# OpenBookReaderC_v7.net
KiCad netlist of a schematic drawn in EAGLE
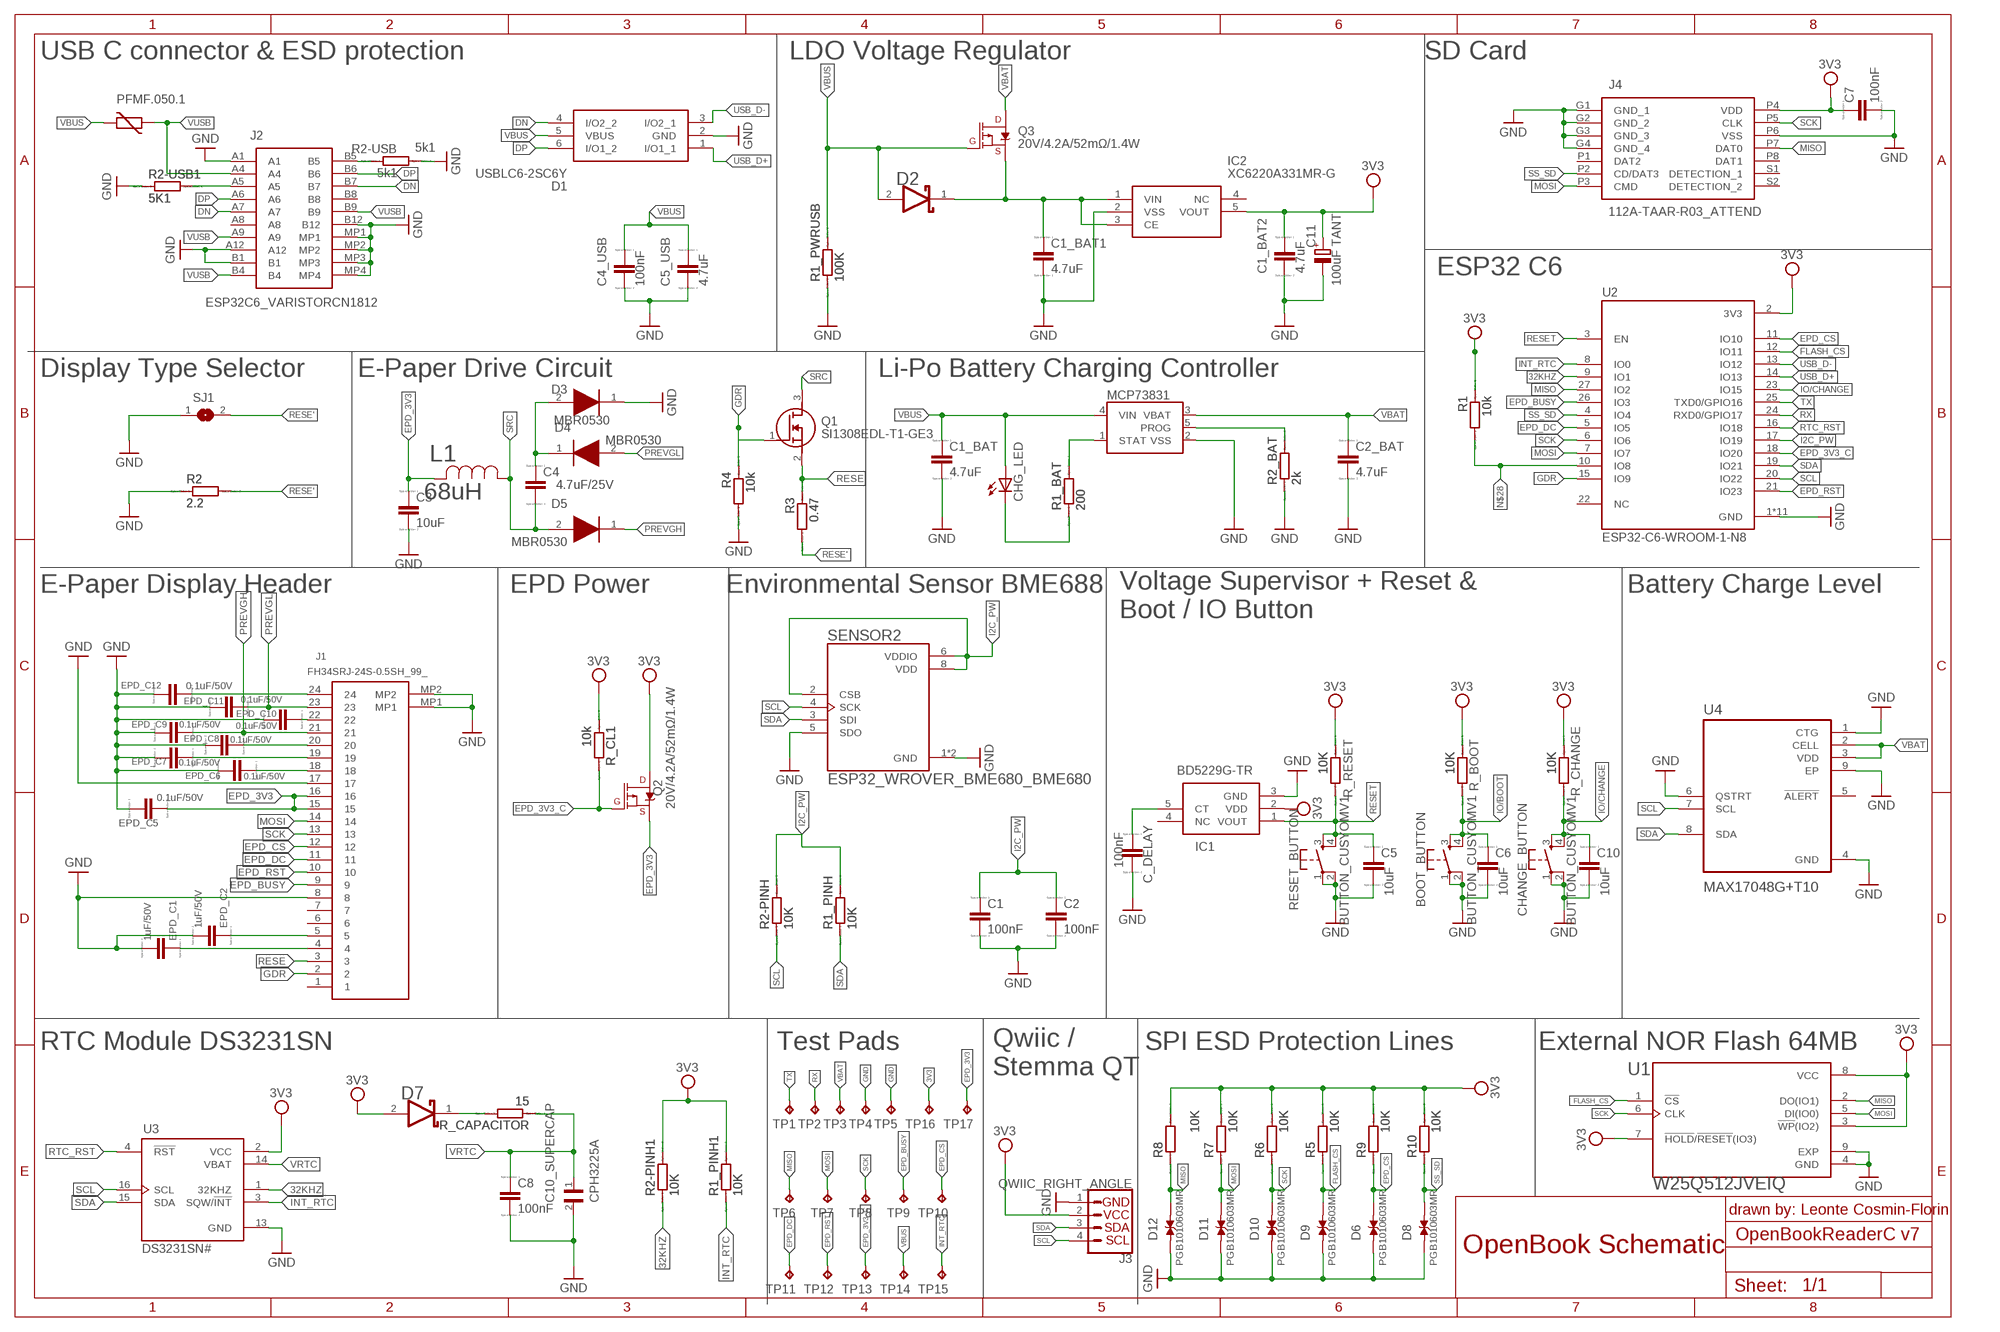
[diagram p0: schematic, sheet 1]

(export (version "E")
  (design (tool "Eeschema 10.0.6"))
  (components
    (comp (ref "BOOT_BUTTON")
      (value "BUTTON_CUSYOMV1")
      (footprint "eagle-import:MYBUTTON")
      (libsource (lib "eagle-import") (part "BUTTON_CUSYOMV1"))
    )
    (comp (ref "C1")
      (value "100nF")
      (footprint "eagle-import:ESP32_WROVER_EAGLE-LTSPICE_C0402")
      (libsource (lib "eagle-import") (part "ESP32_WROVER_EAGLE-LTSPICE_CC0402"))
    )
    (comp (ref "C1_BAT")
      (value "4.7uF")
      (footprint "eagle-import:ESP32_WROVER_EAGLE-LTSPICE_C0402")
      (libsource (lib "eagle-import") (part "ESP32_WROVER_EAGLE-LTSPICE_CC0402"))
    )
    (comp (ref "C1_BAT1")
      (value "4.7uF")
      (footprint "eagle-import:ESP32_WROVER_EAGLE-LTSPICE_C0402")
      (libsource (lib "eagle-import") (part "ESP32_WROVER_EAGLE-LTSPICE_CC0402"))
    )
    (comp (ref "C1_BAT2")
      (value "4.7uF")
      (footprint "eagle-import:ESP32_WROVER_EAGLE-LTSPICE_C0402")
      (libsource (lib "eagle-import") (part "ESP32_WROVER_EAGLE-LTSPICE_CC0402"))
    )
    (comp (ref "C2")
      (value "100nF")
      (footprint "eagle-import:ESP32_WROVER_EAGLE-LTSPICE_C0402")
      (libsource (lib "eagle-import") (part "ESP32_WROVER_EAGLE-LTSPICE_CC0402"))
    )
    (comp (ref "C2_BAT")
      (value "4.7uF")
      (footprint "eagle-import:ESP32_WROVER_EAGLE-LTSPICE_C0402")
      (libsource (lib "eagle-import") (part "ESP32_WROVER_EAGLE-LTSPICE_CC0402"))
    )
    (comp (ref "C3")
      (value "10uF")
      (footprint "eagle-import:ESP32_WROVER_EAGLE-LTSPICE_C0402")
      (libsource (lib "eagle-import") (part "ESP32_WROVER_EAGLE-LTSPICE_CC0402"))
    )
    (comp (ref "C4")
      (value "4.7uF/25V")
      (footprint "eagle-import:ESP32_WROVER_EAGLE-LTSPICE_C0402")
      (libsource (lib "eagle-import") (part "DeskAssistant_v19_v1_vf.EQLOxIDGRNyRrnCg3211Tg_ESP32_WROVER_EAGLE-LTSPICE_CC0402"))
    )
    (comp (ref "C4_USB")
      (value "100nF")
      (footprint "eagle-import:ESP32_WROVER_EAGLE-LTSPICE_C0402")
      (libsource (lib "eagle-import") (part "ESP32_WROVER_EAGLE-LTSPICE_CC0402"))
    )
    (comp (ref "C5")
      (value "10uF")
      (footprint "eagle-import:ESP32_WROVER_EAGLE-LTSPICE_C0402")
      (libsource (lib "eagle-import") (part "ESP32_WROVER_EAGLE-LTSPICE_CC0402"))
    )
    (comp (ref "C5_USB")
      (value "4.7uF")
      (footprint "eagle-import:ESP32_WROVER_EAGLE-LTSPICE_C0402")
      (libsource (lib "eagle-import") (part "ESP32_WROVER_EAGLE-LTSPICE_CC0402"))
    )
    (comp (ref "C6")
      (value "10uF")
      (footprint "eagle-import:ESP32_WROVER_EAGLE-LTSPICE_C0402")
      (libsource (lib "eagle-import") (part "ESP32_WROVER_EAGLE-LTSPICE_CC0402"))
    )
    (comp (ref "C7")
      (value "100nF")
      (footprint "eagle-import:ESP32_WROVER_EAGLE-LTSPICE_C0402")
      (libsource (lib "eagle-import") (part "ESP32_WROVER_EAGLE-LTSPICE_CC0402"))
    )
    (comp (ref "C8")
      (value "100nF")
      (footprint "eagle-import:ESP32_WROVER_EAGLE-LTSPICE_C0402")
      (libsource (lib "eagle-import") (part "ESP32_WROVER_EAGLE-LTSPICE_CC0402"))
    )
    (comp (ref "C10")
      (value "10uF")
      (footprint "eagle-import:ESP32_WROVER_EAGLE-LTSPICE_C0402")
      (libsource (lib "eagle-import") (part "ESP32_WROVER_EAGLE-LTSPICE_CC0402"))
    )
    (comp (ref "C10_SUPERCAP")
      (value "CPH3225A")
      (footprint "eagle-import:CAPCP3225X100N")
      (fields (field (name "MF") "Seiko Instruments"))
      (libsource (lib "eagle-import") (part "CPH3225A"))
    )
    (comp (ref "C11")
      (value "100uF TANT")
      (footprint "eagle-import:RCL_CT3528")
      (libsource (lib "eagle-import") (part "RCL_CPOL-EUCT3528"))
    )
    (comp (ref "CHANGE_BUTTON")
      (value "BUTTON_CUSYOMV1")
      (footprint "eagle-import:MYBUTTON")
      (libsource (lib "eagle-import") (part "BUTTON_CUSYOMV1"))
    )
    (comp (ref "CHG_LED")
      (value "ADAFRUIT_LEDCHIP-LED0603")
      (footprint "eagle-import:ADAFRUIT_CHIP-LED0603")
      (libsource (lib "eagle-import") (part "ADAFRUIT_LEDCHIP-LED0603"))
    )
    (comp (ref "C_DELAY")
      (value "100nF")
      (footprint "eagle-import:ESP32_WROVER_EAGLE-LTSPICE_C0402")
      (libsource (lib "eagle-import") (part "ESP32_WROVER_EAGLE-LTSPICE_CC0402"))
    )
    (comp (ref "D1")
      (value "USBLC6-2SC6Y")
      (footprint "eagle-import:SOT95P280X145-6N")
      (fields (field (name "MF") "STMicroelectronics"))
      (libsource (lib "eagle-import") (part "USBLC6-2SC6Y"))
    )
    (comp (ref "D2")
      (value "ESP32_WROVER_AVX---SD0805S020S1R0_AVX_SD0805S020S1R0_0_0AVX_SD0805S020S1R0_0_0")
      (footprint "eagle-import:ESP32_WROVER_AVX---SD0805S020S1R0_AVX_SD0805S020S1R0_0")
      (fields
        (field (name "DIGIKEY_PART_NUMBER") "478-7800-1-ND")
        (field (name "MF") "AVX")
        (field (name "MOUSER_PART_NUMBER") "581-SD0805S020S1R0")
      )
      (libsource (lib "eagle-import") (part "ESP32_WROVER_AVX---SD0805S020S1R0_AVX_SD0805S020S1R0_0_0AVX_SD0805S020S1R0_0_0"))
    )
    (comp (ref "D3")
      (value "MBR0530")
      (footprint "eagle-import:SOD3716X135N")
      (fields (field (name "MF") "ON Semiconductor"))
      (libsource (lib "eagle-import") (part "MBR0530"))
    )
    (comp (ref "D4")
      (value "MBR0530")
      (footprint "eagle-import:SOD3716X135N")
      (fields (field (name "MF") "ON Semiconductor"))
      (libsource (lib "eagle-import") (part "MBR0530"))
    )
    (comp (ref "D5")
      (value "MBR0530")
      (footprint "eagle-import:SOD3716X135N")
      (fields (field (name "MF") "ON Semiconductor"))
      (libsource (lib "eagle-import") (part "MBR0530"))
    )
    (comp (ref "D6")
      (value "PGB1010603MR")
      (footprint "eagle-import:DIOC1608X36N")
      (fields (field (name "MF") "Littelfuse Inc."))
      (libsource (lib "eagle-import") (part "PGB1010603MR"))
    )
    (comp (ref "D7")
      (value "ESP32_WROVER_AVX---SD0805S020S1R0_AVX_SD0805S020S1R0_0_0AVX_SD0805S020S1R0_0_0")
      (footprint "eagle-import:ESP32_WROVER_AVX---SD0805S020S1R0_AVX_SD0805S020S1R0_0")
      (fields
        (field (name "DIGIKEY_PART_NUMBER") "478-7800-1-ND")
        (field (name "MF") "AVX")
        (field (name "MOUSER_PART_NUMBER") "581-SD0805S020S1R0")
      )
      (libsource (lib "eagle-import") (part "ESP32_WROVER_AVX---SD0805S020S1R0_AVX_SD0805S020S1R0_0_0AVX_SD0805S020S1R0_0_0"))
    )
    (comp (ref "D8")
      (value "PGB1010603MR")
      (footprint "eagle-import:DIOC1608X36N")
      (fields (field (name "MF") "Littelfuse Inc."))
      (libsource (lib "eagle-import") (part "PGB1010603MR"))
    )
    (comp (ref "D9")
      (value "PGB1010603MR")
      (footprint "eagle-import:DIOC1608X36N")
      (fields (field (name "MF") "Littelfuse Inc."))
      (libsource (lib "eagle-import") (part "PGB1010603MR"))
    )
    (comp (ref "D10")
      (value "PGB1010603MR")
      (footprint "eagle-import:DIOC1608X36N")
      (fields (field (name "MF") "Littelfuse Inc."))
      (libsource (lib "eagle-import") (part "PGB1010603MR"))
    )
    (comp (ref "D11")
      (value "PGB1010603MR")
      (footprint "eagle-import:DIOC1608X36N")
      (fields (field (name "MF") "Littelfuse Inc."))
      (libsource (lib "eagle-import") (part "PGB1010603MR"))
    )
    (comp (ref "D12")
      (value "PGB1010603MR")
      (footprint "eagle-import:DIOC1608X36N")
      (fields (field (name "MF") "Littelfuse Inc."))
      (libsource (lib "eagle-import") (part "PGB1010603MR"))
    )
    (comp (ref "EPD_C1")
      (value "1uF/50V")
      (footprint "eagle-import:ESP32_WROVER_EAGLE-LTSPICE_C0402")
      (libsource (lib "eagle-import") (part "ESP32_WROVER_EAGLE-LTSPICE_CC0402"))
    )
    (comp (ref "EPD_C2")
      (value "1uF/50V")
      (footprint "eagle-import:ESP32_WROVER_EAGLE-LTSPICE_C0402")
      (libsource (lib "eagle-import") (part "ESP32_WROVER_EAGLE-LTSPICE_CC0402"))
    )
    (comp (ref "EPD_C5")
      (value "0.1uF/50V")
      (footprint "eagle-import:ESP32_WROVER_EAGLE-LTSPICE_C0402")
      (libsource (lib "eagle-import") (part "ESP32_WROVER_EAGLE-LTSPICE_CC0402"))
    )
    (comp (ref "EPD_C6")
      (value "0.1uF/50V")
      (footprint "eagle-import:ESP32_WROVER_EAGLE-LTSPICE_C0402")
      (libsource (lib "eagle-import") (part "ESP32_WROVER_EAGLE-LTSPICE_CC0402"))
    )
    (comp (ref "EPD_C7")
      (value "0.1uF/50V")
      (footprint "eagle-import:ESP32_WROVER_EAGLE-LTSPICE_C0402")
      (libsource (lib "eagle-import") (part "ESP32_WROVER_EAGLE-LTSPICE_CC0402"))
    )
    (comp (ref "EPD_C8")
      (value "0.1uF/50V")
      (footprint "eagle-import:ESP32_WROVER_EAGLE-LTSPICE_C0402")
      (libsource (lib "eagle-import") (part "ESP32_WROVER_EAGLE-LTSPICE_CC0402"))
    )
    (comp (ref "EPD_C9")
      (value "0.1uF/50V")
      (footprint "eagle-import:ESP32_WROVER_EAGLE-LTSPICE_C0402")
      (libsource (lib "eagle-import") (part "ESP32_WROVER_EAGLE-LTSPICE_CC0402"))
    )
    (comp (ref "EPD_C10")
      (value "0.1uF/50V")
      (footprint "eagle-import:ESP32_WROVER_EAGLE-LTSPICE_C0402")
      (libsource (lib "eagle-import") (part "ESP32_WROVER_EAGLE-LTSPICE_CC0402"))
    )
    (comp (ref "EPD_C11")
      (value "0.1uF/50V")
      (footprint "eagle-import:ESP32_WROVER_EAGLE-LTSPICE_C0402")
      (libsource (lib "eagle-import") (part "ESP32_WROVER_EAGLE-LTSPICE_CC0402"))
    )
    (comp (ref "EPD_C12")
      (value "0.1uF/50V")
      (footprint "eagle-import:ESP32_WROVER_EAGLE-LTSPICE_C0402")
      (libsource (lib "eagle-import") (part "ESP32_WROVER_EAGLE-LTSPICE_CC0402"))
    )
    (comp (ref "IC1")
      (value "BD5229G-TR")
      (footprint "eagle-import:SOT95P280X125-5N")
      (fields (field (name "MOUSER_PART_NUMBER") "755-BD5229G-TR"))
      (libsource (lib "eagle-import") (part "BD5229G-TR"))
    )
    (comp (ref "IC2")
      (value "XC6220A331MR-G")
      (footprint "eagle-import:SOT95P280X120-5N")
      (fields (field (name "MOUSER_PART_NUMBER") "865-XC6220A331MR-G"))
      (libsource (lib "eagle-import") (part "XC6220A331MR-G"))
    )
    (comp (ref "J1")
      (value "FH34SRJ-24S-0.5SH_99_")
      (footprint "eagle-import:FH34SRJ24S05SH99")
      (fields
        (field (name "MANUFACTURER_PART_NUMBER") "FH34SRJ-24S-0.5SH(99)")
        (field (name "MOUSER_PART_NUMBER") "798-FH34SRJ24S05SH99")
      )
      (libsource (lib "eagle-import") (part "FH34SRJ-24S-0.5SH_99_"))
    )
    (comp (ref "J2")
      (value "SAMACSYS_PARTS_USB4110-GF-A")
      (footprint "eagle-import:SAMACSYS_PARTS_USB4110GFA")
      (fields
        (field (name "MANUFACTURER_PART_NUMBER") "USB4110-GF-A")
        (field (name "MOUSER_PART_NUMBER") "640-USB4110-GF-A")
      )
      (libsource (lib "eagle-import") (part "SAMACSYS_PARTS_USB4110-GF-A"))
    )
    (comp (ref "J3")
      (value "QWIIC_RIGHT_ANGLE")
      (footprint "eagle-import:JST04_1MM_RA")
      (libsource (lib "eagle-import") (part "QWIIC_CONNECTORJS-1MM"))
    )
    (comp (ref "J4")
      (value "112A-TAAR-R03_ATTEND")
      (footprint "eagle-import:112ATAARR03ATTEND")
      (fields (field (name "MANUFACTURER_PART_NUMBER") "112A-TAAR-R03 ATTEND"))
      (libsource (lib "eagle-import") (part "112A-TAAR-R03_ATTEND"))
    )
    (comp (ref "L1")
      (value "68uH")
      (footprint "eagle-import:IND_4828-WE-TPC_WRE")
      (fields
        (field (name "MANUFACTURER_PART_NUMBER") "744043680")
        (field (name "COPYRIGHT") "Copyright (C) 2024 Ultra Librarian. All rights reserved.")
      )
      (libsource (lib "eagle-import") (part "744043680IND_4828-WE-TPC_WRE"))
    )
    (comp (ref "MCP73831")
      (value "ESP32_WROVER_SPARKFUN-IC-POWER_MCP73831")
      (footprint "eagle-import:ESP32_WROVER_SPARKFUN-IC-POWER_SOT23-5")
      (libsource (lib "eagle-import") (part "ESP32_WROVER_SPARKFUN-IC-POWER_MCP73831"))
    )
    (comp (ref "PFMF.050.1")
      (value "ESP32C6_VARISTORCN1812")
      (footprint "eagle-import:ESP32C6_VARISTOR_CT_CN1812")
      (libsource (lib "eagle-import") (part "ESP32C6_VARISTORCN1812"))
    )
    (comp (ref "Q1")
      (value "SI1308EDL-T1-GE3")
      (footprint "eagle-import:SOT65P210X110-3N")
      (fields (field (name "MF") "Vishay Siliconix"))
      (libsource (lib "eagle-import") (part "SI1308EDL-T1-GE3"))
    )
    (comp (ref "Q2")
      (value "20V/4.2A/52mΩ/1.4W")
      (footprint "eagle-import:ESP32_WROVER_SPARKFUN-DISCRETESEMI_SOT23-3")
      (libsource (lib "eagle-import") (part "ESP32_WROVER_SPARKFUN-DISCRETESEMI_MOSFET_PCH-DMG2305UX-7"))
    )
    (comp (ref "Q3")
      (value "20V/4.2A/52mΩ/1.4W")
      (footprint "eagle-import:ESP32_WROVER_SPARKFUN-DISCRETESEMI_SOT23-3")
      (libsource (lib "eagle-import") (part "ESP32_WROVER_SPARKFUN-DISCRETESEMI_MOSFET_PCH-DMG2305UX-7"))
    )
    (comp (ref "R1")
      (value "10k")
      (footprint "eagle-import:ESP32_WROVER_EAGLE-LTSPICE_R0402")
      (libsource (lib "eagle-import") (part "DeskAssistant_v19_v1_vf.EQLOxIDGRNyRrnCg3211Tg_ESP32_WROVER_EAGLE-LTSPICE_RR0402"))
    )
    (comp (ref "R1_BAT")
      (value "200")
      (footprint "eagle-import:ESP32_WROVER_EAGLE-LTSPICE_R0402")
      (libsource (lib "eagle-import") (part "DeskAssistant_v19_v1_vf.EQLOxIDGRNyRrnCg3211Tg_ESP32_WROVER_EAGLE-LTSPICE_RR0402"))
    )
    (comp (ref "R1_PINH")
      (value "10K")
      (footprint "eagle-import:ESP32_WROVER_EAGLE-LTSPICE_R0402")
      (libsource (lib "eagle-import") (part "DeskAssistant_v19_v1_vf.EQLOxIDGRNyRrnCg3211Tg_ESP32_WROVER_EAGLE-LTSPICE_RR0402"))
    )
    (comp (ref "R1_PINH1")
      (value "10K")
      (footprint "eagle-import:ESP32_WROVER_EAGLE-LTSPICE_R0402")
      (libsource (lib "eagle-import") (part "DeskAssistant_v19_v1_vf.EQLOxIDGRNyRrnCg3211Tg_ESP32_WROVER_EAGLE-LTSPICE_RR0402"))
    )
    (comp (ref "R1_PWRUSB")
      (value "100K")
      (footprint "eagle-import:ESP32_WROVER_EAGLE-LTSPICE_R0402")
      (libsource (lib "eagle-import") (part "DeskAssistant_v19_v1_vf.EQLOxIDGRNyRrnCg3211Tg_ESP32_WROVER_EAGLE-LTSPICE_RR0402"))
    )
    (comp (ref "R2")
      (value "2.2")
      (footprint "eagle-import:ESP32_WROVER_EAGLE-LTSPICE_R0402")
      (libsource (lib "eagle-import") (part "DeskAssistant_v19_v1_vf.EQLOxIDGRNyRrnCg3211Tg_ESP32_WROVER_EAGLE-LTSPICE_RR0402"))
    )
    (comp (ref "R2-PINH")
      (value "10K")
      (footprint "eagle-import:ESP32_WROVER_EAGLE-LTSPICE_R0402")
      (libsource (lib "eagle-import") (part "DeskAssistant_v19_v1_vf.EQLOxIDGRNyRrnCg3211Tg_ESP32_WROVER_EAGLE-LTSPICE_RR0402"))
    )
    (comp (ref "R2-PINH1")
      (value "10K")
      (footprint "eagle-import:ESP32_WROVER_EAGLE-LTSPICE_R0402")
      (libsource (lib "eagle-import") (part "DeskAssistant_v19_v1_vf.EQLOxIDGRNyRrnCg3211Tg_ESP32_WROVER_EAGLE-LTSPICE_RR0402"))
    )
    (comp (ref "R2-USB")
      (value "5k1")
      (footprint "eagle-import:ESP32_WROVER_EAGLE-LTSPICE_R0402")
      (libsource (lib "eagle-import") (part "DeskAssistant_v19_v1_vf.EQLOxIDGRNyRrnCg3211Tg_ESP32_WROVER_EAGLE-LTSPICE_RR0402"))
    )
    (comp (ref "R2-USB1")
      (value "5K1")
      (footprint "eagle-import:ESP32_WROVER_EAGLE-LTSPICE_R0402")
      (libsource (lib "eagle-import") (part "DeskAssistant_v19_v1_vf.EQLOxIDGRNyRrnCg3211Tg_ESP32_WROVER_EAGLE-LTSPICE_RR0402"))
    )
    (comp (ref "R2_BAT")
      (value "2k")
      (footprint "eagle-import:ESP32_WROVER_EAGLE-LTSPICE_R0402")
      (libsource (lib "eagle-import") (part "DeskAssistant_v19_v1_vf.EQLOxIDGRNyRrnCg3211Tg_ESP32_WROVER_EAGLE-LTSPICE_RR0402"))
    )
    (comp (ref "R3")
      (value "0.47")
      (footprint "eagle-import:ESP32_WROVER_EAGLE-LTSPICE_R0402")
      (libsource (lib "eagle-import") (part "ESP32_WROVER_EAGLE-LTSPICE_RR0402"))
    )
    (comp (ref "R4")
      (value "10k")
      (footprint "eagle-import:ESP32_WROVER_EAGLE-LTSPICE_R0402")
      (libsource (lib "eagle-import") (part "ESP32_WROVER_EAGLE-LTSPICE_RR0402"))
    )
    (comp (ref "R5")
      (value "10K")
      (footprint "eagle-import:ESP32_WROVER_EAGLE-LTSPICE_R0402")
      (libsource (lib "eagle-import") (part "DeskAssistant_v19_v1_vf.EQLOxIDGRNyRrnCg3211Tg_ESP32_WROVER_EAGLE-LTSPICE_RR0402"))
    )
    (comp (ref "R6")
      (value "10K")
      (footprint "eagle-import:ESP32_WROVER_EAGLE-LTSPICE_R0402")
      (libsource (lib "eagle-import") (part "DeskAssistant_v19_v1_vf.EQLOxIDGRNyRrnCg3211Tg_ESP32_WROVER_EAGLE-LTSPICE_RR0402"))
    )
    (comp (ref "R7")
      (value "10K")
      (footprint "eagle-import:ESP32_WROVER_EAGLE-LTSPICE_R0402")
      (libsource (lib "eagle-import") (part "DeskAssistant_v19_v1_vf.EQLOxIDGRNyRrnCg3211Tg_ESP32_WROVER_EAGLE-LTSPICE_RR0402"))
    )
    (comp (ref "R8")
      (value "10K")
      (footprint "eagle-import:ESP32_WROVER_EAGLE-LTSPICE_R0402")
      (libsource (lib "eagle-import") (part "DeskAssistant_v19_v1_vf.EQLOxIDGRNyRrnCg3211Tg_ESP32_WROVER_EAGLE-LTSPICE_RR0402"))
    )
    (comp (ref "R9")
      (value "10K")
      (footprint "eagle-import:ESP32_WROVER_EAGLE-LTSPICE_R0402")
      (libsource (lib "eagle-import") (part "DeskAssistant_v19_v1_vf.EQLOxIDGRNyRrnCg3211Tg_ESP32_WROVER_EAGLE-LTSPICE_RR0402"))
    )
    (comp (ref "R10")
      (value "10K")
      (footprint "eagle-import:ESP32_WROVER_EAGLE-LTSPICE_R0402")
      (libsource (lib "eagle-import") (part "DeskAssistant_v19_v1_vf.EQLOxIDGRNyRrnCg3211Tg_ESP32_WROVER_EAGLE-LTSPICE_RR0402"))
    )
    (comp (ref "RESET_BUTTON")
      (value "BUTTON_CUSYOMV1")
      (footprint "eagle-import:MYBUTTON")
      (libsource (lib "eagle-import") (part "BUTTON_CUSYOMV1"))
    )
    (comp (ref "R_BOOT")
      (value "10K")
      (footprint "eagle-import:ESP32_WROVER_EAGLE-LTSPICE_R0402")
      (libsource (lib "eagle-import") (part "DeskAssistant_v19_v1_vf.EQLOxIDGRNyRrnCg3211Tg_ESP32_WROVER_EAGLE-LTSPICE_RR0402"))
    )
    (comp (ref "R_CAPACITOR")
      (value "15")
      (footprint "eagle-import:ESP32_WROVER_EAGLE-LTSPICE_R0402")
      (libsource (lib "eagle-import") (part "DeskAssistant_v19_v1_vf.EQLOxIDGRNyRrnCg3211Tg_ESP32_WROVER_EAGLE-LTSPICE_RR0402"))
    )
    (comp (ref "R_CHANGE")
      (value "10K")
      (footprint "eagle-import:ESP32_WROVER_EAGLE-LTSPICE_R0402")
      (libsource (lib "eagle-import") (part "DeskAssistant_v19_v1_vf.EQLOxIDGRNyRrnCg3211Tg_ESP32_WROVER_EAGLE-LTSPICE_RR0402"))
    )
    (comp (ref "R_CL1")
      (value "10k")
      (footprint "eagle-import:ESP32_WROVER_EAGLE-LTSPICE_R0402")
      (libsource (lib "eagle-import") (part "DeskAssistant_v19_v1_vf.EQLOxIDGRNyRrnCg3211Tg_ESP32_WROVER_EAGLE-LTSPICE_RR0402"))
    )
    (comp (ref "R_RESET")
      (value "10K")
      (footprint "eagle-import:ESP32_WROVER_EAGLE-LTSPICE_R0402")
      (libsource (lib "eagle-import") (part "DeskAssistant_v19_v1_vf.EQLOxIDGRNyRrnCg3211Tg_ESP32_WROVER_EAGLE-LTSPICE_RR0402"))
    )
    (comp (ref "SENSOR2")
      (value "ESP32_WROVER_BME680_BME680")
      (footprint "eagle-import:ESP32_WROVER_BME680_PSON80P300X300X100-8N")
      (fields (field (name "MF") "Bosch Sensortec") (field (name "MP") "BME680"))
      (libsource (lib "eagle-import") (part "ESP32_WROVER_BME680_BME680"))
    )
    (comp (ref "SJ1") (value "SJ") (footprint "eagle-import:SJ") (libsource (lib "eagle-import") (part "SJ")))
    (comp (ref "TP1")
      (value "TPTP20R")
      (footprint "eagle-import:TP20R")
      (libsource (lib "eagle-import") (part "TPTP20R"))
    )
    (comp (ref "TP2")
      (value "TPTP20R")
      (footprint "eagle-import:TP20R")
      (libsource (lib "eagle-import") (part "TPTP20R"))
    )
    (comp (ref "TP3")
      (value "TPTP20R")
      (footprint "eagle-import:TP20R")
      (libsource (lib "eagle-import") (part "TPTP20R"))
    )
    (comp (ref "TP4")
      (value "TPTP20R")
      (footprint "eagle-import:TP20R")
      (libsource (lib "eagle-import") (part "TPTP20R"))
    )
    (comp (ref "TP5")
      (value "TPTP20R")
      (footprint "eagle-import:TP20R")
      (libsource (lib "eagle-import") (part "TPTP20R"))
    )
    (comp (ref "TP6")
      (value "TPTP20R")
      (footprint "eagle-import:TP20R")
      (libsource (lib "eagle-import") (part "TPTP20R"))
    )
    (comp (ref "TP7")
      (value "TPTP20R")
      (footprint "eagle-import:TP20R")
      (libsource (lib "eagle-import") (part "TPTP20R"))
    )
    (comp (ref "TP8")
      (value "TPTP20R")
      (footprint "eagle-import:TP20R")
      (libsource (lib "eagle-import") (part "TPTP20R"))
    )
    (comp (ref "TP9")
      (value "TPTP20R")
      (footprint "eagle-import:TP20R")
      (libsource (lib "eagle-import") (part "TPTP20R"))
    )
    (comp (ref "TP10")
      (value "TPTP20R")
      (footprint "eagle-import:TP20R")
      (libsource (lib "eagle-import") (part "TPTP20R"))
    )
    (comp (ref "TP11")
      (value "TPTP20R")
      (footprint "eagle-import:TP20R")
      (libsource (lib "eagle-import") (part "TPTP20R"))
    )
    (comp (ref "TP12")
      (value "TPTP20R")
      (footprint "eagle-import:TP20R")
      (libsource (lib "eagle-import") (part "TPTP20R"))
    )
    (comp (ref "TP13")
      (value "TPTP20R")
      (footprint "eagle-import:TP20R")
      (libsource (lib "eagle-import") (part "TPTP20R"))
    )
    (comp (ref "TP14")
      (value "TPTP20R")
      (footprint "eagle-import:TP20R")
      (libsource (lib "eagle-import") (part "TPTP20R"))
    )
    (comp (ref "TP15")
      (value "TPTP20R")
      (footprint "eagle-import:TP20R")
      (libsource (lib "eagle-import") (part "TPTP20R"))
    )
    (comp (ref "TP16")
      (value "TPTP20R")
      (footprint "eagle-import:TP20R")
      (libsource (lib "eagle-import") (part "TPTP20R"))
    )
    (comp (ref "TP17")
      (value "TPTP20R")
      (footprint "eagle-import:TP20R")
      (libsource (lib "eagle-import") (part "TPTP20R"))
    )
    (comp (ref "U1")
      (value "W25Q512JVEIQ")
      (footprint "eagle-import:SON127P600X800X80-9N")
      (fields (field (name "MF") "Winbond Electronics"))
      (libsource (lib "eagle-import") (part "W25Q512JVEIQ"))
    )
    (comp (ref "U2")
      (value "ESP32-C6-WROOM-1-N8")
      (footprint "eagle-import:XCVR_ESP32-C6-WROOM-1-N8")
      (fields (field (name "MF") "Espressif Systems"))
      (libsource (lib "eagle-import") (part "ESP32-C6-WROOM-1-N8"))
    )
    (comp (ref "U3")
      (value "DS3231SN#")
      (footprint "eagle-import:SOIC127P1032X265-16N")
      (fields (field (name "MF") "Analog Devices"))
      (libsource (lib "eagle-import") (part "DS3231SN#"))
    )
    (comp (ref "U4")
      (value "MAX17048G+T10")
      (footprint "eagle-import:SON50P200X200X80-9N")
      (fields (field (name "MF") "Analog Devices"))
      (libsource (lib "eagle-import") (part "MAX17048G+T10"))
    )
  )
  (nets
    (net (code "1") (name "3V3") (class "Default")
      (node (ref "C11") (pin "+") (pinfunction "+_+") (pintype "passive"))
      (node (ref "C1_BAT2") (pin "1") (pinfunction "1_1") (pintype "passive"))
      (node (ref "C7") (pin "1") (pinfunction "1_1") (pintype "passive"))
      (node (ref "D7") (pin "2") (pinfunction "ANODE_2") (pintype "bidirectional"))
      (node (ref "IC1") (pin "2") (pinfunction "VDD_2") (pintype "bidirectional"))
      (node (ref "IC2") (pin "5") (pinfunction "VOUT_5") (pintype "bidirectional"))
      (node (ref "J3") (pin "2") (pinfunction "2_2") (pintype "power_in"))
      (node (ref "J4") (pin "P4") (pinfunction "VDD_P4") (pintype "bidirectional"))
      (node (ref "Q2") (pin "3") (pinfunction "D_3") (pintype "bidirectional"))
      (node (ref "R1") (pin "1") (pinfunction "1_1") (pintype "passive"))
      (node (ref "R10") (pin "2") (pinfunction "2_2") (pintype "passive"))
      (node (ref "R1_PINH1") (pin "2") (pinfunction "2_2") (pintype "passive"))
      (node (ref "R2-PINH1") (pin "2") (pinfunction "2_2") (pintype "passive"))
      (node (ref "R5") (pin "2") (pinfunction "2_2") (pintype "passive"))
      (node (ref "R6") (pin "2") (pinfunction "2_2") (pintype "passive"))
      (node (ref "R7") (pin "2") (pinfunction "2_2") (pintype "passive"))
      (node (ref "R8") (pin "2") (pinfunction "2_2") (pintype "passive"))
      (node (ref "R9") (pin "2") (pinfunction "2_2") (pintype "passive"))
      (node (ref "R_BOOT") (pin "1") (pinfunction "1_1") (pintype "passive"))
      (node (ref "R_CHANGE") (pin "1") (pinfunction "1_1") (pintype "passive"))
      (node (ref "R_CL1") (pin "1") (pinfunction "1_1") (pintype "passive"))
      (node (ref "R_RESET") (pin "1") (pinfunction "1_1") (pintype "passive"))
      (node (ref "TP16") (pin "TP") (pinfunction "TP_TP") (pintype "input"))
      (node (ref "U1") (pin "3") (pinfunction "~{WP}(IO2)_3") (pintype "bidirectional"))
      (node (ref "U1") (pin "7") (pinfunction "~{HOLD}/~{RESET}(IO3)_7") (pintype "bidirectional"))
      (node (ref "U1") (pin "8") (pinfunction "VCC_8") (pintype "power_in"))
      (node (ref "U2") (pin "2") (pinfunction "3V3_2") (pintype "power_in"))
      (node (ref "U3") (pin "2") (pinfunction "VCC_2") (pintype "power_in"))
    )
    (net (code "2") (name "32KHZ") (class "Default")
      (node (ref "R2-PINH1") (pin "1") (pinfunction "1_1") (pintype "passive"))
      (node (ref "U2") (pin "9") (pinfunction "IO1_9") (pintype "bidirectional"))
      (node (ref "U3") (pin "1") (pinfunction "32KHZ_1") (pintype "output"))
    )
    (net (code "3") (name "DN") (class "Default")
      (node (ref "D1") (pin "4") (pinfunction "I/O2_2_4") (pintype "bidirectional"))
      (node (ref "J2") (pin "A7") (pinfunction "A7_A7") (pintype "bidirectional"))
      (node (ref "J2") (pin "B7") (pinfunction "B7_B7") (pintype "bidirectional"))
    )
    (net (code "4") (name "DP") (class "Default")
      (node (ref "D1") (pin "6") (pinfunction "I/O1_2_6") (pintype "bidirectional"))
      (node (ref "J2") (pin "A6") (pinfunction "A6_A6") (pintype "bidirectional"))
      (node (ref "J2") (pin "B6") (pinfunction "B6_B6") (pintype "bidirectional"))
    )
    (net (code "5") (name "EPD_3V3") (class "Default")
      (node (ref "C3") (pin "1") (pinfunction "1_1") (pintype "passive"))
      (node (ref "EPD_C5") (pin "1") (pinfunction "1_1") (pintype "passive"))
      (node (ref "J1") (pin "15") (pinfunction "15_15") (pintype "bidirectional"))
      (node (ref "J1") (pin "16") (pinfunction "16_16") (pintype "bidirectional"))
      (node (ref "L1") (pin "2") (pinfunction "2_2") (pintype "passive"))
      (node (ref "Q2") (pin "2") (pinfunction "S_2") (pintype "bidirectional"))
      (node (ref "TP17") (pin "TP") (pinfunction "TP_TP") (pintype "input"))
    )
    (net (code "6") (name "EPD_3V3_C") (class "Default")
      (node (ref "Q2") (pin "1") (pinfunction "G_1") (pintype "bidirectional"))
      (node (ref "R_CL1") (pin "2") (pinfunction "2_2") (pintype "passive"))
      (node (ref "TP13") (pin "TP") (pinfunction "TP_TP") (pintype "input"))
      (node (ref "U2") (pin "18") (pinfunction "IO20_18") (pintype "bidirectional"))
    )
    (net (code "7") (name "EPD_BUSY") (class "Default")
      (node (ref "J1") (pin "9") (pinfunction "9_9") (pintype "bidirectional"))
      (node (ref "TP9") (pin "TP") (pinfunction "TP_TP") (pintype "input"))
      (node (ref "U2") (pin "26") (pinfunction "IO3_26") (pintype "bidirectional"))
    )
    (net (code "8") (name "EPD_CS") (class "Default")
      (node (ref "D6") (pin "2") (pinfunction "2_2") (pintype "passive"))
      (node (ref "J1") (pin "12") (pinfunction "12_12") (pintype "bidirectional"))
      (node (ref "R9") (pin "1") (pinfunction "1_1") (pintype "passive"))
      (node (ref "TP10") (pin "TP") (pinfunction "TP_TP") (pintype "input"))
      (node (ref "U2") (pin "11") (pinfunction "IO10_11") (pintype "bidirectional"))
    )
    (net (code "9") (name "EPD_DC") (class "Default")
      (node (ref "J1") (pin "11") (pinfunction "11_11") (pintype "bidirectional"))
      (node (ref "TP11") (pin "TP") (pinfunction "TP_TP") (pintype "input"))
      (node (ref "U2") (pin "5") (pinfunction "IO5_5") (pintype "bidirectional"))
    )
    (net (code "10") (name "EPD_RST") (class "Default")
      (node (ref "J1") (pin "10") (pinfunction "10_10") (pintype "bidirectional"))
      (node (ref "TP12") (pin "TP") (pinfunction "TP_TP") (pintype "input"))
      (node (ref "U2") (pin "21") (pinfunction "IO23_21") (pintype "bidirectional"))
    )
    (net (code "11") (name "FLASH_CS") (class "Default")
      (node (ref "D9") (pin "2") (pinfunction "2_2") (pintype "passive"))
      (node (ref "R5") (pin "1") (pinfunction "1_1") (pintype "passive"))
      (node (ref "U1") (pin "1") (pinfunction "~{CS}_1") (pintype "input"))
      (node (ref "U2") (pin "12") (pinfunction "IO11_12") (pintype "bidirectional"))
    )
    (net (code "12") (name "GDR") (class "Default")
      (node (ref "J1") (pin "2") (pinfunction "2_2") (pintype "bidirectional"))
      (node (ref "Q1") (pin "1") (pinfunction "G_1") (pintype "bidirectional"))
      (node (ref "R4") (pin "1") (pinfunction "1_1") (pintype "passive"))
      (node (ref "U2") (pin "15") (pinfunction "IO9_15") (pintype "bidirectional"))
    )
    (net (code "13") (name "GND") (class "Default")
      (node (ref "BOOT_BUTTON") (pin "1") (pinfunction "1_1") (pintype "passive"))
      (node (ref "BOOT_BUTTON") (pin "2") (pinfunction "2_2") (pintype "passive"))
      (node (ref "C1") (pin "2") (pinfunction "2_2") (pintype "passive"))
      (node (ref "C10") (pin "2") (pinfunction "2_2") (pintype "passive"))
      (node (ref "C10_SUPERCAP") (pin "2") (pinfunction "2_2") (pintype "passive"))
      (node (ref "C11") (pin "-") (pinfunction "-_-") (pintype "passive"))
      (node (ref "C1_BAT") (pin "2") (pinfunction "2_2") (pintype "passive"))
      (node (ref "C1_BAT1") (pin "2") (pinfunction "2_2") (pintype "passive"))
      (node (ref "C1_BAT2") (pin "2") (pinfunction "2_2") (pintype "passive"))
      (node (ref "C2") (pin "2") (pinfunction "2_2") (pintype "passive"))
      (node (ref "C2_BAT") (pin "2") (pinfunction "2_2") (pintype "passive"))
      (node (ref "C3") (pin "2") (pinfunction "2_2") (pintype "passive"))
      (node (ref "C4_USB") (pin "2") (pinfunction "2_2") (pintype "passive"))
      (node (ref "C5") (pin "2") (pinfunction "2_2") (pintype "passive"))
      (node (ref "C5_USB") (pin "2") (pinfunction "2_2") (pintype "passive"))
      (node (ref "C6") (pin "2") (pinfunction "2_2") (pintype "passive"))
      (node (ref "C7") (pin "2") (pinfunction "2_2") (pintype "passive"))
      (node (ref "C8") (pin "2") (pinfunction "2_2") (pintype "passive"))
      (node (ref "CHANGE_BUTTON") (pin "1") (pinfunction "1_1") (pintype "passive"))
      (node (ref "CHANGE_BUTTON") (pin "2") (pinfunction "2_2") (pintype "passive"))
      (node (ref "C_DELAY") (pin "2") (pinfunction "2_2") (pintype "passive"))
      (node (ref "D1") (pin "2") (pinfunction "GND_2") (pintype "bidirectional"))
      (node (ref "D10") (pin "1") (pinfunction "1_1") (pintype "passive"))
      (node (ref "D11") (pin "1") (pinfunction "1_1") (pintype "passive"))
      (node (ref "D12") (pin "1") (pinfunction "1_1") (pintype "passive"))
      (node (ref "D3") (pin "1") (pinfunction "K_1") (pintype "bidirectional"))
      (node (ref "D6") (pin "1") (pinfunction "1_1") (pintype "passive"))
      (node (ref "D8") (pin "1") (pinfunction "1_1") (pintype "passive"))
      (node (ref "D9") (pin "1") (pinfunction "1_1") (pintype "passive"))
      (node (ref "EPD_C1") (pin "2") (pinfunction "2_2") (pintype "passive"))
      (node (ref "EPD_C10") (pin "2") (pinfunction "2_2") (pintype "passive"))
      (node (ref "EPD_C11") (pin "2") (pinfunction "2_2") (pintype "passive"))
      (node (ref "EPD_C12") (pin "2") (pinfunction "2_2") (pintype "passive"))
      (node (ref "EPD_C2") (pin "2") (pinfunction "2_2") (pintype "passive"))
      (node (ref "EPD_C5") (pin "2") (pinfunction "2_2") (pintype "passive"))
      (node (ref "EPD_C6") (pin "2") (pinfunction "2_2") (pintype "passive"))
      (node (ref "EPD_C7") (pin "2") (pinfunction "2_2") (pintype "passive"))
      (node (ref "EPD_C8") (pin "2") (pinfunction "2_2") (pintype "passive"))
      (node (ref "EPD_C9") (pin "2") (pinfunction "2_2") (pintype "passive"))
      (node (ref "IC1") (pin "3") (pinfunction "GND_3") (pintype "bidirectional"))
      (node (ref "IC2") (pin "2") (pinfunction "VSS_2") (pintype "bidirectional"))
      (node (ref "J1") (pin "17") (pinfunction "17_17") (pintype "bidirectional"))
      (node (ref "J1") (pin "8") (pinfunction "8_8") (pintype "bidirectional"))
      (node (ref "J1") (pin "MP1") (pinfunction "MP1_MP1") (pintype "bidirectional"))
      (node (ref "J1") (pin "MP2") (pinfunction "MP2_MP2") (pintype "bidirectional"))
      (node (ref "J2") (pin "A1") (pinfunction "A1_A1") (pintype "bidirectional"))
      (node (ref "J2") (pin "A12") (pinfunction "A12_A12") (pintype "bidirectional"))
      (node (ref "J2") (pin "B1") (pinfunction "B1_B1") (pintype "bidirectional"))
      (node (ref "J2") (pin "B12") (pinfunction "B12_B12") (pintype "bidirectional"))
      (node (ref "J2") (pin "MP1") (pinfunction "MP1_MP1") (pintype "bidirectional"))
      (node (ref "J2") (pin "MP2") (pinfunction "MP2_MP2") (pintype "bidirectional"))
      (node (ref "J2") (pin "MP3") (pinfunction "MP3_MP3") (pintype "bidirectional"))
      (node (ref "J2") (pin "MP4") (pinfunction "MP4_MP4") (pintype "bidirectional"))
      (node (ref "J3") (pin "1") (pinfunction "1_1") (pintype "power_in"))
      (node (ref "J4") (pin "G1") (pinfunction "GND_1_G1") (pintype "bidirectional"))
      (node (ref "J4") (pin "G2") (pinfunction "GND_2_G2") (pintype "bidirectional"))
      (node (ref "J4") (pin "G3") (pinfunction "GND_3_G3") (pintype "bidirectional"))
      (node (ref "J4") (pin "G4") (pinfunction "GND_4_G4") (pintype "bidirectional"))
      (node (ref "J4") (pin "P6") (pinfunction "VSS_P6") (pintype "bidirectional"))
      (node (ref "MCP73831") (pin "2") (pinfunction "VSS_2") (pintype "power_in"))
      (node (ref "R1_PWRUSB") (pin "1") (pinfunction "1_1") (pintype "passive"))
      (node (ref "R2") (pin "1") (pinfunction "1_1") (pintype "passive"))
      (node (ref "R2-USB") (pin "2") (pinfunction "2_2") (pintype "passive"))
      (node (ref "R2-USB1") (pin "1") (pinfunction "1_1") (pintype "passive"))
      (node (ref "R2_BAT") (pin "1") (pinfunction "1_1") (pintype "passive"))
      (node (ref "R4") (pin "2") (pinfunction "2_2") (pintype "passive"))
      (node (ref "RESET_BUTTON") (pin "1") (pinfunction "1_1") (pintype "passive"))
      (node (ref "RESET_BUTTON") (pin "2") (pinfunction "2_2") (pintype "passive"))
      (node (ref "SENSOR2") (pin "1") (pinfunction "GND_1") (pintype "power_in"))
      (node (ref "SENSOR2") (pin "5") (pinfunction "SDO_5") (pintype "bidirectional"))
      (node (ref "SENSOR2") (pin "7") (pinfunction "GND_7") (pintype "power_in"))
      (node (ref "SJ1") (pin "1") (pinfunction "1_1") (pintype "passive"))
      (node (ref "TP4") (pin "TP") (pinfunction "TP_TP") (pintype "input"))
      (node (ref "TP5") (pin "TP") (pinfunction "TP_TP") (pintype "input"))
      (node (ref "U1") (pin "4") (pinfunction "GND_4") (pintype "power_in"))
      (node (ref "U1") (pin "9") (pinfunction "EXP_9") (pintype "passive"))
      (node (ref "U2") (pin "1") (pinfunction "GND_1") (pintype "power_in"))
      (node (ref "U2") (pin "28") (pinfunction "GND_28") (pintype "power_in"))
      (node (ref "U2") (pin "29_1") (pinfunction "GND_29_1") (pintype "power_in"))
      (node (ref "U2") (pin "29_2") (pinfunction "GND_29_2") (pintype "power_in"))
      (node (ref "U2") (pin "29_3") (pinfunction "GND_29_3") (pintype "power_in"))
      (node (ref "U2") (pin "29_4") (pinfunction "GND_29_4") (pintype "power_in"))
      (node (ref "U2") (pin "29_5") (pinfunction "GND_29_5") (pintype "power_in"))
      (node (ref "U2") (pin "29_6") (pinfunction "GND_29_6") (pintype "power_in"))
      (node (ref "U2") (pin "29_7") (pinfunction "GND_29_7") (pintype "power_in"))
      (node (ref "U2") (pin "29_8") (pinfunction "GND_29_8") (pintype "power_in"))
      (node (ref "U2") (pin "29_9") (pinfunction "GND_29_9") (pintype "power_in"))
      (node (ref "U3") (pin "13") (pinfunction "GND_13") (pintype "power_in"))
      (node (ref "U4") (pin "1") (pinfunction "CTG_1") (pintype "power_in"))
      (node (ref "U4") (pin "4") (pinfunction "GND_4") (pintype "power_in"))
      (node (ref "U4") (pin "6") (pinfunction "QSTRT_6") (pintype "input"))
      (node (ref "U4") (pin "9") (pinfunction "EP_9") (pintype "power_in"))
    )
    (net (code "14") (name "I2C_PW") (class "Default")
      (node (ref "C1") (pin "1") (pinfunction "1_1") (pintype "passive"))
      (node (ref "C2") (pin "1") (pinfunction "1_1") (pintype "passive"))
      (node (ref "R1_PINH") (pin "2") (pinfunction "2_2") (pintype "passive"))
      (node (ref "R2-PINH") (pin "2") (pinfunction "2_2") (pintype "passive"))
      (node (ref "SENSOR2") (pin "2") (pinfunction "CSB_2") (pintype "input"))
      (node (ref "SENSOR2") (pin "6") (pinfunction "VDDIO_6") (pintype "power_in"))
      (node (ref "SENSOR2") (pin "8") (pinfunction "VDD_8") (pintype "power_in"))
      (node (ref "U2") (pin "17") (pinfunction "IO19_17") (pintype "bidirectional"))
    )
    (net (code "15") (name "INT_RTC") (class "Default")
      (node (ref "R1_PINH1") (pin "1") (pinfunction "1_1") (pintype "passive"))
      (node (ref "TP15") (pin "TP") (pinfunction "TP_TP") (pintype "input"))
      (node (ref "U2") (pin "8") (pinfunction "IO0_8") (pintype "bidirectional"))
      (node (ref "U3") (pin "3") (pinfunction "SQW/~{INT}_3") (pintype "output"))
    )
    (net (code "16") (name "IO{slash}BOOT") (class "Default")
      (node (ref "BOOT_BUTTON") (pin "3") (pinfunction "3_3") (pintype "passive"))
      (node (ref "BOOT_BUTTON") (pin "4") (pinfunction "4_4") (pintype "passive"))
      (node (ref "C6") (pin "1") (pinfunction "1_1") (pintype "passive"))
      (node (ref "R_BOOT") (pin "2") (pinfunction "2_2") (pintype "passive"))
    )
    (net (code "17") (name "IO{slash}CHANGE") (class "Default")
      (node (ref "C10") (pin "1") (pinfunction "1_1") (pintype "passive"))
      (node (ref "CHANGE_BUTTON") (pin "3") (pinfunction "3_3") (pintype "passive"))
      (node (ref "CHANGE_BUTTON") (pin "4") (pinfunction "4_4") (pintype "passive"))
      (node (ref "R_CHANGE") (pin "2") (pinfunction "2_2") (pintype "passive"))
      (node (ref "U2") (pin "23") (pinfunction "IO15_23") (pintype "bidirectional"))
    )
    (net (code "18") (name "MISO") (class "Default")
      (node (ref "D12") (pin "2") (pinfunction "2_2") (pintype "passive"))
      (node (ref "J4") (pin "P7") (pinfunction "DAT0_P7") (pintype "bidirectional"))
      (node (ref "R8") (pin "1") (pinfunction "1_1") (pintype "passive"))
      (node (ref "TP6") (pin "TP") (pinfunction "TP_TP") (pintype "input"))
      (node (ref "U1") (pin "2") (pinfunction "DO(IO1)_2") (pintype "bidirectional"))
      (node (ref "U2") (pin "27") (pinfunction "IO2_27") (pintype "bidirectional"))
    )
    (net (code "19") (name "MOSI") (class "Default")
      (node (ref "D11") (pin "2") (pinfunction "2_2") (pintype "passive"))
      (node (ref "J1") (pin "14") (pinfunction "14_14") (pintype "bidirectional"))
      (node (ref "J4") (pin "P3") (pinfunction "CMD_P3") (pintype "bidirectional"))
      (node (ref "R7") (pin "1") (pinfunction "1_1") (pintype "passive"))
      (node (ref "TP7") (pin "TP") (pinfunction "TP_TP") (pintype "input"))
      (node (ref "U1") (pin "5") (pinfunction "DI(IO0)_5") (pintype "bidirectional"))
      (node (ref "U2") (pin "7") (pinfunction "IO7_7") (pintype "bidirectional"))
    )
    (net (code "20") (name "N$28") (class "Default")
      (node (ref "R1") (pin "2") (pinfunction "2_2") (pintype "passive"))
      (node (ref "U2") (pin "10") (pinfunction "IO8_10") (pintype "bidirectional"))
    )
    (net (code "21") (name "Net-(CHG_LED-PadC)") (class "Default")
      (node (ref "CHG_LED") (pin "C") (pinfunction "C_C") (pintype "passive"))
      (node (ref "R1_BAT") (pin "1") (pinfunction "1_1") (pintype "passive"))
    )
    (net (code "22") (name "Net-(D2-CATHODE)") (class "Default")
      (node (ref "C1_BAT1") (pin "1") (pinfunction "1_1") (pintype "passive"))
      (node (ref "D2") (pin "1") (pinfunction "CATHODE_1") (pintype "bidirectional"))
      (node (ref "IC2") (pin "1") (pinfunction "VIN_1") (pintype "bidirectional"))
      (node (ref "IC2") (pin "3") (pinfunction "CE_3") (pintype "bidirectional"))
      (node (ref "Q3") (pin "2") (pinfunction "S_2") (pintype "bidirectional"))
    )
    (net (code "23") (name "Net-(D3-A)") (class "Default")
      (node (ref "C4") (pin "1") (pinfunction "1_1") (pintype "passive"))
      (node (ref "D3") (pin "2") (pinfunction "A_2") (pintype "bidirectional"))
      (node (ref "D4") (pin "1") (pinfunction "K_1") (pintype "bidirectional"))
    )
    (net (code "24") (name "Net-(D7-CATHODE)") (class "Default")
      (node (ref "D7") (pin "1") (pinfunction "CATHODE_1") (pintype "bidirectional"))
      (node (ref "R_CAPACITOR") (pin "2") (pinfunction "2_2") (pintype "passive"))
    )
    (net (code "25") (name "Net-(EPD_C1-Pad1)") (class "Default")
      (node (ref "EPD_C1") (pin "1") (pinfunction "1_1") (pintype "passive"))
      (node (ref "J1") (pin "4") (pinfunction "4_4") (pintype "bidirectional"))
    )
    (net (code "26") (name "Net-(EPD_C2-Pad1)") (class "Default")
      (node (ref "EPD_C2") (pin "1") (pinfunction "1_1") (pintype "passive"))
      (node (ref "J1") (pin "5") (pinfunction "5_5") (pintype "bidirectional"))
    )
    (net (code "27") (name "Net-(EPD_C6-Pad1)") (class "Default")
      (node (ref "EPD_C6") (pin "1") (pinfunction "1_1") (pintype "passive"))
      (node (ref "J1") (pin "18") (pinfunction "18_18") (pintype "bidirectional"))
    )
    (net (code "28") (name "Net-(EPD_C7-Pad1)") (class "Default")
      (node (ref "EPD_C7") (pin "1") (pinfunction "1_1") (pintype "passive"))
      (node (ref "J1") (pin "19") (pinfunction "19_19") (pintype "bidirectional"))
    )
    (net (code "29") (name "Net-(EPD_C8-Pad1)") (class "Default")
      (node (ref "EPD_C8") (pin "1") (pinfunction "1_1") (pintype "passive"))
      (node (ref "J1") (pin "20") (pinfunction "20_20") (pintype "bidirectional"))
    )
    (net (code "30") (name "Net-(EPD_C10-Pad1)") (class "Default")
      (node (ref "EPD_C10") (pin "1") (pinfunction "1_1") (pintype "passive"))
      (node (ref "J1") (pin "22") (pinfunction "22_22") (pintype "bidirectional"))
    )
    (net (code "31") (name "Net-(EPD_C12-Pad1)") (class "Default")
      (node (ref "EPD_C12") (pin "1") (pinfunction "1_1") (pintype "passive"))
      (node (ref "J1") (pin "24") (pinfunction "24_24") (pintype "bidirectional"))
    )
    (net (code "32") (name "Net-(IC1-CT)") (class "Default")
      (node (ref "C_DELAY") (pin "1") (pinfunction "1_1") (pintype "passive"))
      (node (ref "IC1") (pin "5") (pinfunction "CT_5") (pintype "bidirectional"))
    )
    (net (code "33") (name "Net-(J2-PadA5)") (class "Default")
      (node (ref "J2") (pin "A5") (pinfunction "A5_A5") (pintype "bidirectional"))
      (node (ref "R2-USB1") (pin "2") (pinfunction "2_2") (pintype "passive"))
    )
    (net (code "34") (name "Net-(J2-PadB5)") (class "Default")
      (node (ref "J2") (pin "B5") (pinfunction "B5_B5") (pintype "bidirectional"))
      (node (ref "R2-USB") (pin "1") (pinfunction "1_1") (pintype "passive"))
    )
    (net (code "35") (name "Net-(MCP73831-PROG)") (class "Default")
      (node (ref "MCP73831") (pin "5") (pinfunction "PROG_5") (pintype "input"))
      (node (ref "R2_BAT") (pin "2") (pinfunction "2_2") (pintype "passive"))
    )
    (net (code "36") (name "Net-(MCP73831-STAT)") (class "Default")
      (node (ref "MCP73831") (pin "1") (pinfunction "STAT_1") (pintype "output"))
      (node (ref "R1_BAT") (pin "2") (pinfunction "2_2") (pintype "passive"))
    )
    (net (code "37") (name "PREVGH") (class "Default")
      (node (ref "D5") (pin "1") (pinfunction "K_1") (pintype "bidirectional"))
      (node (ref "EPD_C9") (pin "1") (pinfunction "1_1") (pintype "passive"))
      (node (ref "J1") (pin "21") (pinfunction "21_21") (pintype "bidirectional"))
    )
    (net (code "38") (name "PREVGL") (class "Default")
      (node (ref "D4") (pin "2") (pinfunction "A_2") (pintype "bidirectional"))
      (node (ref "EPD_C11") (pin "1") (pinfunction "1_1") (pintype "passive"))
      (node (ref "J1") (pin "23") (pinfunction "23_23") (pintype "bidirectional"))
    )
    (net (code "39") (name "RESE") (class "Default")
      (node (ref "J1") (pin "3") (pinfunction "3_3") (pintype "bidirectional"))
      (node (ref "Q1") (pin "2") (pinfunction "S_2") (pintype "bidirectional"))
      (node (ref "R3") (pin "1") (pinfunction "1_1") (pintype "passive"))
    )
    (net (code "40") (name "RESE'") (class "Default")
      (node (ref "R2") (pin "2") (pinfunction "2_2") (pintype "passive"))
      (node (ref "R3") (pin "2") (pinfunction "2_2") (pintype "passive"))
      (node (ref "SJ1") (pin "2") (pinfunction "2_2") (pintype "passive"))
    )
    (net (code "41") (name "RESET") (class "Default")
      (node (ref "C5") (pin "1") (pinfunction "1_1") (pintype "passive"))
      (node (ref "IC1") (pin "1") (pinfunction "VOUT_1") (pintype "bidirectional"))
      (node (ref "RESET_BUTTON") (pin "3") (pinfunction "3_3") (pintype "passive"))
      (node (ref "RESET_BUTTON") (pin "4") (pinfunction "4_4") (pintype "passive"))
      (node (ref "R_RESET") (pin "2") (pinfunction "2_2") (pintype "passive"))
      (node (ref "U2") (pin "3") (pinfunction "EN_3") (pintype "input"))
    )
    (net (code "42") (name "RTC_RST") (class "Default")
      (node (ref "U2") (pin "16") (pinfunction "IO18_16") (pintype "bidirectional"))
      (node (ref "U3") (pin "4") (pinfunction "~{RST}_4") (pintype "input"))
    )
    (net (code "43") (name "RX") (class "Default")
      (node (ref "TP2") (pin "TP") (pinfunction "TP_TP") (pintype "input"))
      (node (ref "U2") (pin "24") (pinfunction "RXD0/GPIO17_24") (pintype "bidirectional"))
    )
    (net (code "44") (name "SCK") (class "Default")
      (node (ref "D10") (pin "2") (pinfunction "2_2") (pintype "passive"))
      (node (ref "J1") (pin "13") (pinfunction "13_13") (pintype "bidirectional"))
      (node (ref "J4") (pin "P5") (pinfunction "CLK_P5") (pintype "bidirectional"))
      (node (ref "R6") (pin "1") (pinfunction "1_1") (pintype "passive"))
      (node (ref "TP8") (pin "TP") (pinfunction "TP_TP") (pintype "input"))
      (node (ref "U1") (pin "6") (pinfunction "CLK_6") (pintype "input"))
      (node (ref "U2") (pin "6") (pinfunction "IO6_6") (pintype "bidirectional"))
    )
    (net (code "45") (name "SCL") (class "Default")
      (node (ref "J3") (pin "4") (pinfunction "4_4") (pintype "passive"))
      (node (ref "R2-PINH") (pin "1") (pinfunction "1_1") (pintype "passive"))
      (node (ref "SENSOR2") (pin "4") (pinfunction "SCK_4") (pintype "input"))
      (node (ref "U2") (pin "20") (pinfunction "IO22_20") (pintype "bidirectional"))
      (node (ref "U3") (pin "16") (pinfunction "SCL_16") (pintype "input"))
      (node (ref "U4") (pin "7") (pinfunction "SCL_7") (pintype "input"))
    )
    (net (code "46") (name "SDA") (class "Default")
      (node (ref "J3") (pin "3") (pinfunction "3_3") (pintype "passive"))
      (node (ref "R1_PINH") (pin "1") (pinfunction "1_1") (pintype "passive"))
      (node (ref "SENSOR2") (pin "3") (pinfunction "SDI_3") (pintype "bidirectional"))
      (node (ref "U2") (pin "19") (pinfunction "IO21_19") (pintype "bidirectional"))
      (node (ref "U3") (pin "15") (pinfunction "SDA_15") (pintype "bidirectional"))
      (node (ref "U4") (pin "8") (pinfunction "SDA_8") (pintype "bidirectional"))
    )
    (net (code "47") (name "SRC") (class "Default")
      (node (ref "C4") (pin "2") (pinfunction "2_2") (pintype "passive"))
      (node (ref "D5") (pin "2") (pinfunction "A_2") (pintype "bidirectional"))
      (node (ref "L1") (pin "1") (pinfunction "1_1") (pintype "passive"))
      (node (ref "Q1") (pin "3") (pinfunction "D_3") (pintype "bidirectional"))
    )
    (net (code "48") (name "SS_SD") (class "Default")
      (node (ref "D8") (pin "2") (pinfunction "2_2") (pintype "passive"))
      (node (ref "J4") (pin "P2") (pinfunction "CD/DAT3_P2") (pintype "bidirectional"))
      (node (ref "R10") (pin "1") (pinfunction "1_1") (pintype "passive"))
      (node (ref "U2") (pin "4") (pinfunction "IO4_4") (pintype "bidirectional"))
    )
    (net (code "49") (name "TX") (class "Default")
      (node (ref "TP1") (pin "TP") (pinfunction "TP_TP") (pintype "input"))
      (node (ref "U2") (pin "25") (pinfunction "TXD0/GPIO16_25") (pintype "bidirectional"))
    )
    (net (code "50") (name "USB_D+") (class "Default")
      (node (ref "D1") (pin "1") (pinfunction "I/O1_1_1") (pintype "bidirectional"))
      (node (ref "U2") (pin "14") (pinfunction "IO13_14") (pintype "bidirectional"))
    )
    (net (code "51") (name "USB_D-") (class "Default")
      (node (ref "D1") (pin "3") (pinfunction "I/O2_1_3") (pintype "bidirectional"))
      (node (ref "U2") (pin "13") (pinfunction "IO12_13") (pintype "bidirectional"))
    )
    (net (code "52") (name "VBAT") (class "Default")
      (node (ref "C2_BAT") (pin "1") (pinfunction "1_1") (pintype "passive"))
      (node (ref "MCP73831") (pin "3") (pinfunction "VBAT_3") (pintype "power_in"))
      (node (ref "Q3") (pin "3") (pinfunction "D_3") (pintype "bidirectional"))
      (node (ref "TP3") (pin "TP") (pinfunction "TP_TP") (pintype "input"))
      (node (ref "U4") (pin "2") (pinfunction "CELL_2") (pintype "power_in"))
      (node (ref "U4") (pin "3") (pinfunction "VDD_3") (pintype "power_in"))
    )
    (net (code "53") (name "VBUS") (class "Default")
      (node (ref "C1_BAT") (pin "1") (pinfunction "1_1") (pintype "passive"))
      (node (ref "C4_USB") (pin "1") (pinfunction "1_1") (pintype "passive"))
      (node (ref "C5_USB") (pin "1") (pinfunction "1_1") (pintype "passive"))
      (node (ref "CHG_LED") (pin "A") (pinfunction "A_A") (pintype "passive"))
      (node (ref "D1") (pin "5") (pinfunction "VBUS_5") (pintype "bidirectional"))
      (node (ref "D2") (pin "2") (pinfunction "ANODE_2") (pintype "bidirectional"))
      (node (ref "MCP73831") (pin "4") (pinfunction "VIN_4") (pintype "power_in"))
      (node (ref "PFMF.050.1") (pin "2") (pinfunction "2_2") (pintype "passive"))
      (node (ref "Q3") (pin "1") (pinfunction "G_1") (pintype "bidirectional"))
      (node (ref "R1_PWRUSB") (pin "2") (pinfunction "2_2") (pintype "passive"))
      (node (ref "TP14") (pin "TP") (pinfunction "TP_TP") (pintype "input"))
    )
    (net (code "54") (name "VRTC") (class "Default")
      (node (ref "C10_SUPERCAP") (pin "1") (pinfunction "1_1") (pintype "passive"))
      (node (ref "C8") (pin "1") (pinfunction "1_1") (pintype "passive"))
      (node (ref "R_CAPACITOR") (pin "1") (pinfunction "1_1") (pintype "passive"))
      (node (ref "U3") (pin "14") (pinfunction "VBAT_14") (pintype "power_in"))
    )
    (net (code "55") (name "VUSB") (class "Default")
      (node (ref "J2") (pin "A4") (pinfunction "A4_A4") (pintype "bidirectional"))
      (node (ref "J2") (pin "A9") (pinfunction "A9_A9") (pintype "bidirectional"))
      (node (ref "J2") (pin "B4") (pinfunction "B4_B4") (pintype "bidirectional"))
      (node (ref "J2") (pin "B9") (pinfunction "B9_B9") (pintype "bidirectional"))
      (node (ref "PFMF.050.1") (pin "1") (pinfunction "1_1") (pintype "passive"))
    )
    (net (code "56") (name "unconnected-(IC1-NC-Pad4)") (class "Default")
      (node (ref "IC1") (pin "4") (pinfunction "NC_4") (pintype "no_connect"))
    )
    (net (code "57") (name "unconnected-(IC2-NC-Pad4)") (class "Default")
      (node (ref "IC2") (pin "4") (pinfunction "NC_4") (pintype "no_connect"))
    )
    (net (code "58") (name "unconnected-(J1-Pad1)") (class "Default")
      (node (ref "J1") (pin "1") (pinfunction "1_1") (pintype "bidirectional"))
    )
    (net (code "59") (name "unconnected-(J1-Pad6)") (class "Default")
      (node (ref "J1") (pin "6") (pinfunction "6_6") (pintype "bidirectional"))
    )
    (net (code "60") (name "unconnected-(J1-Pad7)") (class "Default")
      (node (ref "J1") (pin "7") (pinfunction "7_7") (pintype "bidirectional"))
    )
    (net (code "61") (name "unconnected-(J2-PadA8)") (class "Default")
      (node (ref "J2") (pin "A8") (pinfunction "A8_A8") (pintype "bidirectional"))
    )
    (net (code "62") (name "unconnected-(J2-PadB8)") (class "Default")
      (node (ref "J2") (pin "B8") (pinfunction "B8_B8") (pintype "bidirectional"))
    )
    (net (code "63") (name "unconnected-(J4-DAT1-PadP8)") (class "Default")
      (node (ref "J4") (pin "P8") (pinfunction "DAT1_P8") (pintype "bidirectional"))
    )
    (net (code "64") (name "unconnected-(J4-DAT2-PadP1)") (class "Default")
      (node (ref "J4") (pin "P1") (pinfunction "DAT2_P1") (pintype "bidirectional"))
    )
    (net (code "65") (name "unconnected-(J4-DETECTION_1-PadS1)") (class "Default")
      (node (ref "J4") (pin "S1") (pinfunction "DETECTION_1_S1") (pintype "bidirectional"))
    )
    (net (code "66") (name "unconnected-(J4-DETECTION_2-PadS2)") (class "Default")
      (node (ref "J4") (pin "S2") (pinfunction "DETECTION_2_S2") (pintype "bidirectional"))
    )
    (net (code "67") (name "unconnected-(U2-NC-Pad22)") (class "Default")
      (node (ref "U2") (pin "22") (pinfunction "NC_22") (pintype "no_connect"))
    )
    (net (code "68") (name "unconnected-(U4-~{ALERT}-Pad5)") (class "Default")
      (node (ref "U4") (pin "5") (pinfunction "~{ALERT}_5") (pintype "output"))
    )
  )
)
